# SER.net
KiCad netlist of a schematic drawn in Altium Designer
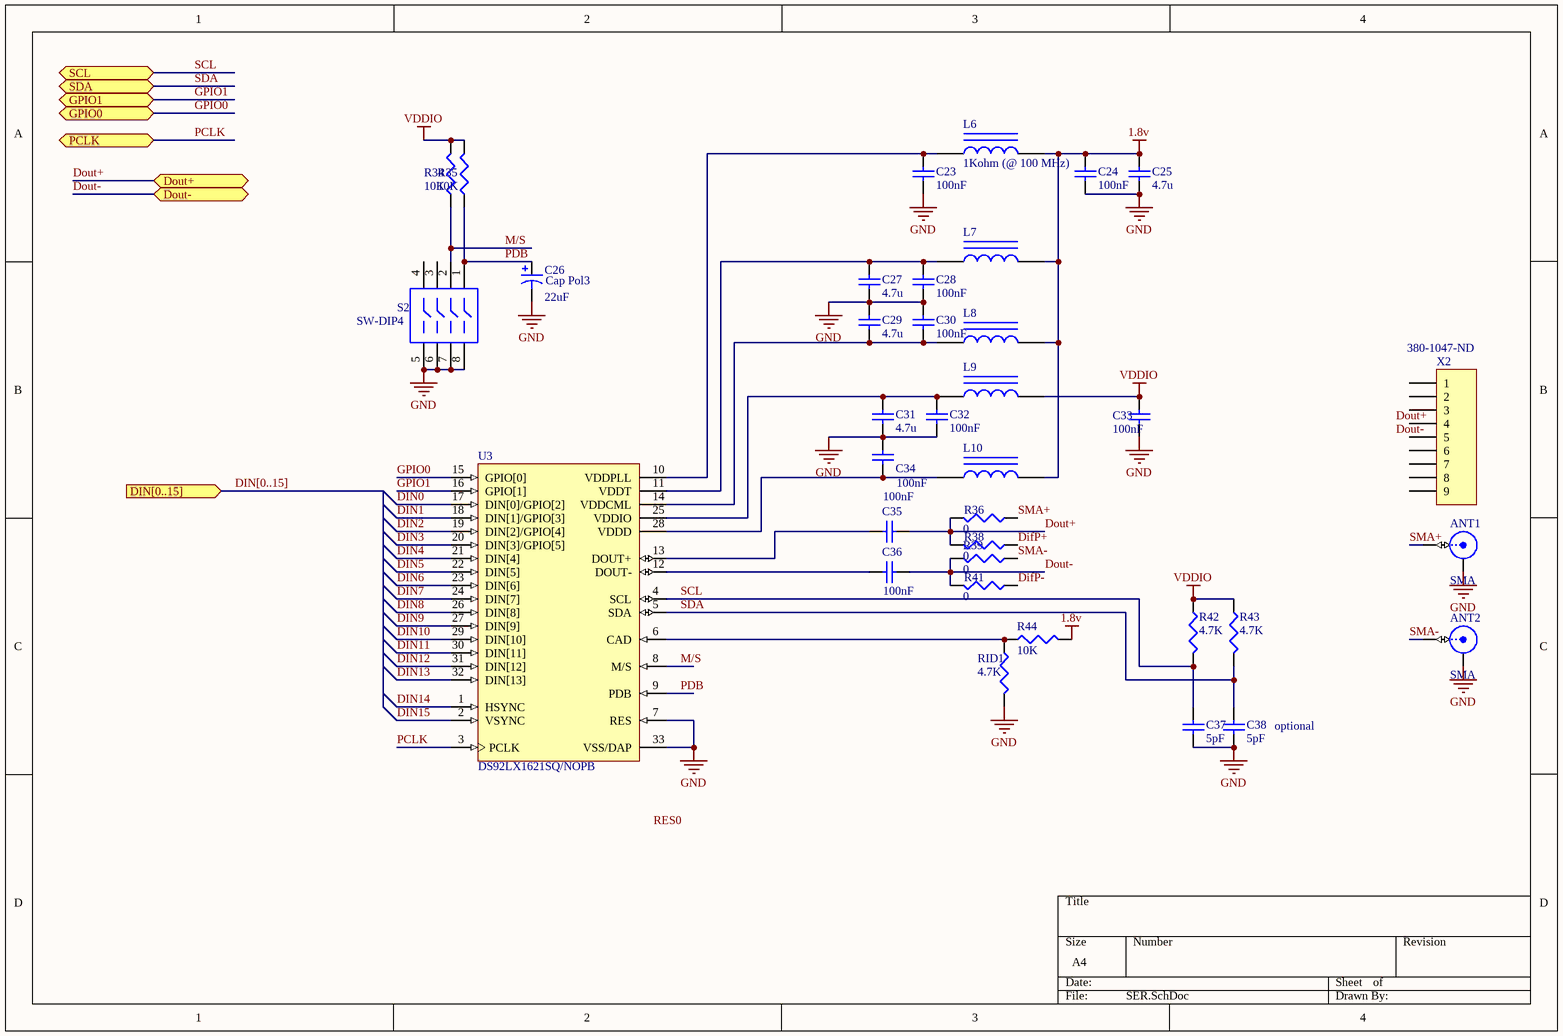
[diagram p0: SER.SchDoc]

(export (version "E")
  (design (tool "Eeschema 10.0.6"))
  (components
    (comp (ref "ANT1")
      (value "SMA")
      (footprint "SMB_V-RJ45")
      (description "SMA 50 Ohm Edge Mount")
      (libsource (lib "Connector_Div_egne") (part "SMA-J-P-H-ST-EM1"))
    )
    (comp (ref "ANT2")
      (value "SMA")
      (footprint "SMB_V-RJ45")
      (description "SMA 50 Ohm Edge Mount")
      (libsource (lib "Connector_Div_egne") (part "SMA-J-P-H-ST-EM1"))
    )
    (comp (ref "C23")
      (value "100nF")
      (footprint "1608[0603]")
      (description "Capacitor (Semiconductor SIM Model)")
      (fields (field (name "Comment") "Cap Semi") (field (name "PUBLISHER") "Altium Limited"))
      (libsource (lib "Miscellaneous Devices") (part "Cap Semi"))
    )
    (comp (ref "C24")
      (value "100nF")
      (footprint "1608[0603]")
      (description "Capacitor (Semiconductor SIM Model)")
      (fields (field (name "Comment") "Cap Semi") (field (name "PUBLISHER") "Altium Limited"))
      (libsource (lib "Miscellaneous Devices") (part "Cap Semi"))
    )
    (comp (ref "C25")
      (value "4.7u")
      (footprint "1608[0603]")
      (description "Capacitor (Semiconductor SIM Model)")
      (fields (field (name "Comment") "Cap Semi") (field (name "PUBLISHER") "Altium Limited"))
      (libsource (lib "Miscellaneous Devices") (part "Cap Semi"))
    )
    (comp (ref "C26")
      (value "Cap Pol3")
      (footprint "C0805")
      (description "Polarized Capacitor (Surface Mount)")
      (fields (field (name "ALTIUM_VALUE") "22uF") (field (name "PUBLISHER") "Altium Limited"))
      (libsource (lib "Miscellaneous Devices") (part "Cap Pol3"))
    )
    (comp (ref "C27")
      (value "4.7u")
      (footprint "1608[0603]")
      (description "Capacitor (Semiconductor SIM Model)")
      (fields (field (name "Comment") "Cap Semi") (field (name "PUBLISHER") "Altium Limited"))
      (libsource (lib "Miscellaneous Devices") (part "Cap Semi"))
    )
    (comp (ref "C28")
      (value "100nF")
      (footprint "1608[0603]")
      (description "Capacitor (Semiconductor SIM Model)")
      (fields (field (name "Comment") "Cap Semi") (field (name "PUBLISHER") "Altium Limited"))
      (libsource (lib "Miscellaneous Devices") (part "Cap Semi"))
    )
    (comp (ref "C29")
      (value "4.7u")
      (footprint "1608[0603]")
      (description "Capacitor (Semiconductor SIM Model)")
      (fields (field (name "Comment") "Cap Semi") (field (name "PUBLISHER") "Altium Limited"))
      (libsource (lib "Miscellaneous Devices") (part "Cap Semi"))
    )
    (comp (ref "C30")
      (value "100nF")
      (footprint "1608[0603]")
      (description "Capacitor (Semiconductor SIM Model)")
      (fields (field (name "Comment") "Cap Semi") (field (name "PUBLISHER") "Altium Limited"))
      (libsource (lib "Miscellaneous Devices") (part "Cap Semi"))
    )
    (comp (ref "C31")
      (value "4.7u")
      (footprint "1608[0603]")
      (description "Capacitor (Semiconductor SIM Model)")
      (fields (field (name "Comment") "Cap Semi") (field (name "PUBLISHER") "Altium Limited"))
      (libsource (lib "Miscellaneous Devices") (part "Cap Semi"))
    )
    (comp (ref "C32")
      (value "100nF")
      (footprint "1608[0603]")
      (description "Capacitor (Semiconductor SIM Model)")
      (fields (field (name "Comment") "Cap Semi") (field (name "PUBLISHER") "Altium Limited"))
      (libsource (lib "Miscellaneous Devices") (part "Cap Semi"))
    )
    (comp (ref "C33")
      (value "100nF")
      (footprint "1608[0603]")
      (description "Capacitor (Semiconductor SIM Model)")
      (fields (field (name "Comment") "Cap Semi") (field (name "PUBLISHER") "Altium Limited"))
      (libsource (lib "Miscellaneous Devices") (part "Cap Semi"))
    )
    (comp (ref "C34")
      (value "100nF")
      (footprint "1608[0603]")
      (description "Capacitor (Semiconductor SIM Model)")
      (fields (field (name "Comment") "Cap Semi") (field (name "PUBLISHER") "Altium Limited"))
      (libsource (lib "Miscellaneous Devices") (part "Cap Semi"))
    )
    (comp (ref "C35")
      (value "100nF")
      (footprint "1608[0603]")
      (description "CAP CER 0.1UF 50V X7R 0603")
      (fields (field (name "Comment") "Cap Semi") (field (name "PUBLISHER") "Altium Limited"))
      (libsource (lib "Miscellaneous Devices") (part "Cap Semi"))
    )
    (comp (ref "C36")
      (value "100nF")
      (footprint "1608[0603]")
      (description "CAP CER 0.1UF 50V X7R 0603")
      (fields (field (name "Comment") "Cap Semi") (field (name "PUBLISHER") "Altium Limited"))
      (libsource (lib "Miscellaneous Devices") (part "Cap Semi"))
    )
    (comp (ref "C37")
      (value "5pF")
      (footprint "1608[0603]")
      (description "Capacitor (Semiconductor SIM Model)")
      (fields (field (name "Comment") "Cap Semi") (field (name "PUBLISHER") "Altium Limited"))
      (libsource (lib "Miscellaneous Devices") (part "Cap Semi"))
    )
    (comp (ref "C38")
      (value "5pF")
      (footprint "1608[0603]")
      (description "Capacitor (Semiconductor SIM Model)")
      (fields (field (name "Comment") "Cap Semi") (field (name "PUBLISHER") "Altium Limited"))
      (libsource (lib "Miscellaneous Devices") (part "Cap Semi"))
    )
    (comp (ref "L6")
      (value "1Kohm (@ 100 MHz)")
      (footprint "0805")
      (description "Impedance = 1Kohm (@ 100 MHz)  low DC resistance (<1ohm)")
      (fields (field (name "PUBLISHER") "Altium Limited"))
      (libsource (lib "Miscellaneous Devices") (part "Inductor Iron"))
    )
    (comp (ref "L7")
      (value "~")
      (footprint "0805")
      (description "Impedance = 1 kohm (@ 100 MHz)  low DC resistance (<1ohm)")
      (fields (field (name "PUBLISHER") "Altium Limited"))
      (libsource (lib "Miscellaneous Devices") (part "Inductor Iron"))
    )
    (comp (ref "L8")
      (value "~")
      (footprint "0805")
      (description "Impedance = 1 kohm (@ 100 MHz)  low DC resistance (<1ohm)")
      (fields (field (name "PUBLISHER") "Altium Limited"))
      (libsource (lib "Miscellaneous Devices") (part "Inductor Iron"))
    )
    (comp (ref "L9")
      (value "~")
      (footprint "0805")
      (description "Impedance = 1 kohm (@ 100 MHz)  low DC resistance (<1ohm)")
      (fields (field (name "PUBLISHER") "Altium Limited"))
      (libsource (lib "Miscellaneous Devices") (part "Inductor Iron"))
    )
    (comp (ref "L10")
      (value "~")
      (footprint "0805")
      (description "Impedance = 1 kohm (@ 100 MHz)  low DC resistance (<1ohm)")
      (fields (field (name "PUBLISHER") "Altium Limited"))
      (libsource (lib "Miscellaneous Devices") (part "Inductor Iron"))
    )
    (comp (ref "R34")
      (value "10K")
      (footprint "12Z-2010")
      (description "Resistor")
      (fields (field (name "Comment") "Res3") (field (name "PUBLISHER") "Altium Limited"))
      (libsource (lib "Miscellaneous Devices") (part "Res3"))
    )
    (comp (ref "R35")
      (value "10K")
      (footprint "12Z-2010")
      (description "Resistor")
      (fields (field (name "Comment") "Res3") (field (name "PUBLISHER") "Altium Limited"))
      (libsource (lib "Miscellaneous Devices") (part "Res3"))
    )
    (comp (ref "R36")
      (value "0")
      (footprint "12Z-2010")
      (description "Resistor")
      (fields (field (name "Comment") "Res3") (field (name "PUBLISHER") "Altium Limited"))
      (libsource (lib "Miscellaneous Devices") (part "Res3"))
    )
    (comp (ref "R38")
      (value "0")
      (footprint "12Z-2010")
      (description "Resistor")
      (fields (field (name "Comment") "Res3") (field (name "PUBLISHER") "Altium Limited"))
      (libsource (lib "Miscellaneous Devices") (part "Res3"))
    )
    (comp (ref "R39")
      (value "0")
      (footprint "12Z-2010")
      (description "Resistor")
      (fields (field (name "Comment") "Res3") (field (name "PUBLISHER") "Altium Limited"))
      (libsource (lib "Miscellaneous Devices") (part "Res3"))
    )
    (comp (ref "R41")
      (value "0")
      (footprint "12Z-2010")
      (description "Resistor")
      (fields (field (name "Comment") "Res3") (field (name "PUBLISHER") "Altium Limited"))
      (libsource (lib "Miscellaneous Devices") (part "Res3"))
    )
    (comp (ref "R42")
      (value "4.7K")
      (footprint "12Z-2010")
      (description "Resistor")
      (fields (field (name "Comment") "Res3") (field (name "PUBLISHER") "Altium Limited"))
      (libsource (lib "Miscellaneous Devices") (part "Res3"))
    )
    (comp (ref "R43")
      (value "4.7K")
      (footprint "12Z-2010")
      (description "Resistor")
      (fields (field (name "Comment") "Res3") (field (name "PUBLISHER") "Altium Limited"))
      (libsource (lib "Miscellaneous Devices") (part "Res3"))
    )
    (comp (ref "R44")
      (value "10K")
      (footprint "12Z-2010")
      (description "Resistor")
      (fields (field (name "Comment") "Res3") (field (name "PUBLISHER") "Altium Limited"))
      (libsource (lib "Miscellaneous Devices") (part "Res3"))
    )
    (comp (ref "RID1")
      (value "4.7K")
      (footprint "12Z-2010")
      (description "Resistor")
      (fields (field (name "Comment") "Res3") (field (name "PUBLISHER") "Altium Limited"))
      (libsource (lib "Miscellaneous Devices") (part "Res3"))
    )
    (comp (ref "S2")
      (value "SW-DIP4")
      (footprint "DIP-8")
      (description "DIP Switch")
      (fields (field (name "PUBLISHER") "Altium Limited"))
      (libsource (lib "Miscellaneous Devices") (part "SW-DIP4"))
    )
    (comp (ref "U3")
      (value "DS92LX1621SQ/NOPB")
      (footprint "SQA32A")
      (description "10 - 50 MHz DC-Balanced Channel Link III Bi-Directional Control Serializer, 32 pin LLP")
      (fields
        (field (name "MANUFACTURER") "National Semiconductor")
        (field (name "PUBLISHER") "Altium Limited")
      )
      (libsource (lib "NSC Interface") (part "DS92LX1621SQ/NOPB"))
    )
    (comp (ref "X2")
      (value "SS-7188S-A-NF")
      (footprint "rj-45")
      (description "CONN MOD JACK 8P8C R/A SHIELDED")
      (fields
        (field (name "SUPPLIER PART NUMBER 1") "380-1047-ND")
        (field (name "MANUFACTURER") "Stewart Connector")
        (field (name "PUBLISHER") "Altium Limited")
      )
      (libsource (lib "Miscellaneous Connectors") (part "Header 9"))
    )
  )
  (nets
    (net (code "1") (name "/DIN0") (class "Default")
      (node (ref "U3") (pin "17") (pinfunction "DIN[0]/GPIO[2]_17") (pintype "input"))
    )
    (net (code "2") (name "/DIN1") (class "Default")
      (node (ref "U3") (pin "18") (pinfunction "DIN[1]/GPIO[3]_18") (pintype "input"))
    )
    (net (code "3") (name "/DIN2") (class "Default")
      (node (ref "U3") (pin "19") (pinfunction "DIN[2]/GPIO[4]_19") (pintype "input"))
    )
    (net (code "4") (name "/DIN3") (class "Default")
      (node (ref "U3") (pin "20") (pinfunction "DIN[3]/GPIO[5]_20") (pintype "input"))
    )
    (net (code "5") (name "/DIN4") (class "Default")
      (node (ref "U3") (pin "21") (pinfunction "DIN[4]_21") (pintype "input"))
    )
    (net (code "6") (name "/DIN5") (class "Default")
      (node (ref "U3") (pin "22") (pinfunction "DIN[5]_22") (pintype "input"))
    )
    (net (code "7") (name "/DIN6") (class "Default")
      (node (ref "U3") (pin "23") (pinfunction "DIN[6]_23") (pintype "input"))
    )
    (net (code "8") (name "/DIN7") (class "Default")
      (node (ref "U3") (pin "24") (pinfunction "DIN[7]_24") (pintype "input"))
    )
    (net (code "9") (name "/DIN8") (class "Default")
      (node (ref "U3") (pin "26") (pinfunction "DIN[8]_26") (pintype "input"))
    )
    (net (code "10") (name "/DIN9") (class "Default")
      (node (ref "U3") (pin "27") (pinfunction "DIN[9]_27") (pintype "input"))
    )
    (net (code "11") (name "/DIN10") (class "Default")
      (node (ref "U3") (pin "29") (pinfunction "DIN[10]_29") (pintype "input"))
    )
    (net (code "12") (name "/DIN11") (class "Default")
      (node (ref "U3") (pin "30") (pinfunction "DIN[11]_30") (pintype "input"))
    )
    (net (code "13") (name "/DIN12") (class "Default")
      (node (ref "U3") (pin "31") (pinfunction "DIN[12]_31") (pintype "input"))
    )
    (net (code "14") (name "/DIN13") (class "Default")
      (node (ref "U3") (pin "32") (pinfunction "DIN[13]_32") (pintype "input"))
    )
    (net (code "15") (name "/DIN14") (class "Default")
      (node (ref "U3") (pin "1") (pinfunction "HSYNC_1") (pintype "input"))
    )
    (net (code "16") (name "/DIN15") (class "Default")
      (node (ref "U3") (pin "2") (pinfunction "VSYNC_2") (pintype "input"))
    )
    (net (code "18") (name "/DifP+") (class "Default")
      (node (ref "R38") (pin "1") (pinfunction "1_1") (pintype "passive"))
    )
    (net (code "19") (name "/DifP-") (class "Default")
      (node (ref "R41") (pin "1") (pinfunction "1_1") (pintype "passive"))
    )
    (net (code "20") (name "/Dout+") (class "Default")
      (node (ref "C35") (pin "2") (pinfunction "2_2") (pintype "passive"))
      (node (ref "R36") (pin "2") (pinfunction "2_2") (pintype "passive"))
      (node (ref "R38") (pin "2") (pinfunction "2_2") (pintype "passive"))
    )
    (net (code "21") (name "/Dout-") (class "Default")
      (node (ref "C36") (pin "2") (pinfunction "2_2") (pintype "passive"))
      (node (ref "R39") (pin "2") (pinfunction "2_2") (pintype "passive"))
      (node (ref "R41") (pin "2") (pinfunction "2_2") (pintype "passive"))
    )
    (net (code "22") (name "/GPIO0") (class "Default")
      (node (ref "U3") (pin "15") (pinfunction "GPIO[0]_15") (pintype "input"))
    )
    (net (code "23") (name "/GPIO1") (class "Default")
      (node (ref "U3") (pin "16") (pinfunction "GPIO[1]_16") (pintype "input"))
    )
    (net (code "24") (name "/M{slash}S") (class "Default")
      (node (ref "R34") (pin "2") (pinfunction "2_2") (pintype "passive"))
      (node (ref "S2") (pin "2") (pinfunction "2_2") (pintype "passive"))
      (node (ref "U3") (pin "8") (pinfunction "M/S_8") (pintype "input"))
    )
    (net (code "25") (name "/PCLK") (class "Default")
      (node (ref "U3") (pin "3") (pinfunction "PCLK_3") (pintype "input"))
    )
    (net (code "26") (name "/PDB") (class "Default")
      (node (ref "C26") (pin "1") (pinfunction "1_1") (pintype "passive"))
      (node (ref "R35") (pin "2") (pinfunction "2_2") (pintype "passive"))
      (node (ref "S2") (pin "1") (pinfunction "1_1") (pintype "passive"))
      (node (ref "U3") (pin "9") (pinfunction "PDB_9") (pintype "input"))
    )
    (net (code "28") (name "/SCL") (class "Default")
      (node (ref "C37") (pin "2") (pinfunction "2_2") (pintype "passive"))
      (node (ref "R42") (pin "2") (pinfunction "2_2") (pintype "passive"))
      (node (ref "U3") (pin "4") (pinfunction "SCL_4") (pintype "bidirectional"))
    )
    (net (code "29") (name "/SDA") (class "Default")
      (node (ref "C38") (pin "2") (pinfunction "2_2") (pintype "passive"))
      (node (ref "R43") (pin "2") (pinfunction "2_2") (pintype "passive"))
      (node (ref "U3") (pin "5") (pinfunction "SDA_5") (pintype "bidirectional"))
    )
    (net (code "30") (name "/SMA+") (class "Default")
      (node (ref "ANT1") (pin "1") (pinfunction "IO_1") (pintype "bidirectional"))
      (node (ref "R36") (pin "1") (pinfunction "1_1") (pintype "passive"))
    )
    (net (code "31") (name "/SMA-") (class "Default")
      (node (ref "ANT2") (pin "1") (pinfunction "IO_1") (pintype "bidirectional"))
      (node (ref "R39") (pin "1") (pinfunction "1_1") (pintype "passive"))
    )
    (net (code "32") (name "1.8v") (class "Default")
      (node (ref "C24") (pin "2") (pinfunction "2_2") (pintype "passive"))
      (node (ref "C25") (pin "2") (pinfunction "2_2") (pintype "passive"))
      (node (ref "L10") (pin "2") (pinfunction "2_2") (pintype "passive"))
      (node (ref "L6") (pin "2") (pinfunction "2_2") (pintype "passive"))
      (node (ref "L7") (pin "2") (pinfunction "2_2") (pintype "passive"))
      (node (ref "L8") (pin "2") (pinfunction "2_2") (pintype "passive"))
      (node (ref "R44") (pin "2") (pinfunction "2_2") (pintype "passive"))
    )
    (net (code "33") (name "GND") (class "Default")
      (node (ref "ANT1") (pin "2") (pinfunction "Y_2") (pintype "power_in"))
      (node (ref "ANT2") (pin "2") (pinfunction "Y_2") (pintype "power_in"))
      (node (ref "C23") (pin "1") (pinfunction "1_1") (pintype "passive"))
      (node (ref "C24") (pin "1") (pinfunction "1_1") (pintype "passive"))
      (node (ref "C25") (pin "1") (pinfunction "1_1") (pintype "passive"))
      (node (ref "C26") (pin "2") (pinfunction "2_2") (pintype "passive"))
      (node (ref "C27") (pin "1") (pinfunction "1_1") (pintype "passive"))
      (node (ref "C28") (pin "1") (pinfunction "1_1") (pintype "passive"))
      (node (ref "C29") (pin "2") (pinfunction "2_2") (pintype "passive"))
      (node (ref "C30") (pin "2") (pinfunction "2_2") (pintype "passive"))
      (node (ref "C31") (pin "1") (pinfunction "1_1") (pintype "passive"))
      (node (ref "C32") (pin "1") (pinfunction "1_1") (pintype "passive"))
      (node (ref "C33") (pin "1") (pinfunction "1_1") (pintype "passive"))
      (node (ref "C34") (pin "2") (pinfunction "2_2") (pintype "passive"))
      (node (ref "C37") (pin "1") (pinfunction "1_1") (pintype "passive"))
      (node (ref "C38") (pin "1") (pinfunction "1_1") (pintype "passive"))
      (node (ref "RID1") (pin "2") (pinfunction "2_2") (pintype "passive"))
      (node (ref "S2") (pin "5") (pinfunction "5_5") (pintype "passive"))
      (node (ref "S2") (pin "6") (pinfunction "6_6") (pintype "passive"))
      (node (ref "S2") (pin "7") (pinfunction "7_7") (pintype "passive"))
      (node (ref "S2") (pin "8") (pinfunction "8_8") (pintype "passive"))
      (node (ref "U3") (pin "33") (pinfunction "VSS/DAP_33") (pintype "power_in"))
      (node (ref "U3") (pin "7") (pinfunction "RES_7") (pintype "input"))
    )
    (net (code "34") (name "Net-(U3-CAD)") (class "Default")
      (node (ref "R44") (pin "1") (pinfunction "1_1") (pintype "passive"))
      (node (ref "RID1") (pin "1") (pinfunction "1_1") (pintype "passive"))
      (node (ref "U3") (pin "6") (pinfunction "CAD_6") (pintype "input"))
    )
    (net (code "35") (name "Net-(U3-DOUT+)") (class "Default")
      (node (ref "C35") (pin "1") (pinfunction "1_1") (pintype "passive"))
      (node (ref "U3") (pin "13") (pinfunction "DOUT+_13") (pintype "bidirectional"))
    )
    (net (code "36") (name "Net-(U3-DOUT-)") (class "Default")
      (node (ref "C36") (pin "1") (pinfunction "1_1") (pintype "passive"))
      (node (ref "U3") (pin "12") (pinfunction "DOUT-_12") (pintype "bidirectional"))
    )
    (net (code "37") (name "Net-(U3-VDDCML)") (class "Default")
      (node (ref "C29") (pin "1") (pinfunction "1_1") (pintype "passive"))
      (node (ref "C30") (pin "1") (pinfunction "1_1") (pintype "passive"))
      (node (ref "L8") (pin "1") (pinfunction "1_1") (pintype "passive"))
      (node (ref "U3") (pin "14") (pinfunction "VDDCML_14") (pintype "power_in"))
    )
    (net (code "38") (name "Net-(U3-VDDD)") (class "Default")
      (node (ref "C34") (pin "1") (pinfunction "1_1") (pintype "passive"))
      (node (ref "L10") (pin "1") (pinfunction "1_1") (pintype "passive"))
      (node (ref "U3") (pin "28") (pinfunction "VDDD_28") (pintype "power_in"))
    )
    (net (code "39") (name "Net-(U3-VDDIO)") (class "Default")
      (node (ref "C31") (pin "2") (pinfunction "2_2") (pintype "passive"))
      (node (ref "C32") (pin "2") (pinfunction "2_2") (pintype "passive"))
      (node (ref "L9") (pin "1") (pinfunction "1_1") (pintype "passive"))
      (node (ref "U3") (pin "25") (pinfunction "VDDIO_25") (pintype "power_in"))
    )
    (net (code "40") (name "Net-(U3-VDDPLL)") (class "Default")
      (node (ref "C23") (pin "2") (pinfunction "2_2") (pintype "passive"))
      (node (ref "L6") (pin "1") (pinfunction "1_1") (pintype "passive"))
      (node (ref "U3") (pin "10") (pinfunction "VDDPLL_10") (pintype "power_in"))
    )
    (net (code "41") (name "Net-(U3-VDDT)") (class "Default")
      (node (ref "C27") (pin "2") (pinfunction "2_2") (pintype "passive"))
      (node (ref "C28") (pin "2") (pinfunction "2_2") (pintype "passive"))
      (node (ref "L7") (pin "1") (pinfunction "1_1") (pintype "passive"))
      (node (ref "U3") (pin "11") (pinfunction "VDDT_11") (pintype "power_in"))
    )
    (net (code "42") (name "VDDIO") (class "Default")
      (node (ref "C33") (pin "2") (pinfunction "2_2") (pintype "passive"))
      (node (ref "L9") (pin "2") (pinfunction "2_2") (pintype "passive"))
      (node (ref "R34") (pin "1") (pinfunction "1_1") (pintype "passive"))
      (node (ref "R35") (pin "1") (pinfunction "1_1") (pintype "passive"))
      (node (ref "R42") (pin "1") (pinfunction "1_1") (pintype "passive"))
      (node (ref "R43") (pin "1") (pinfunction "1_1") (pintype "passive"))
    )
    (net (code "43") (name "unconnected-(S2-Pad3)") (class "Default")
      (node (ref "S2") (pin "3") (pinfunction "3_3") (pintype "passive"))
    )
    (net (code "44") (name "unconnected-(S2-Pad4)") (class "Default")
      (node (ref "S2") (pin "4") (pinfunction "4_4") (pintype "passive"))
    )
    (net (code "45") (name "unconnected-(X2-Pad1)") (class "Default")
      (node (ref "X2") (pin "1") (pinfunction "1_1") (pintype "passive"))
    )
    (net (code "46") (name "unconnected-(X2-Pad2)") (class "Default")
      (node (ref "X2") (pin "2") (pinfunction "2_2") (pintype "passive"))
    )
    (net (code "47") (name "unconnected-(X2-Pad3)") (class "Default")
      (node (ref "X2") (pin "3") (pinfunction "3_3") (pintype "passive"))
    )
    (net (code "48") (name "unconnected-(X2-Pad4)") (class "Default")
      (node (ref "X2") (pin "4") (pinfunction "4_4") (pintype "passive"))
    )
    (net (code "49") (name "unconnected-(X2-Pad5)") (class "Default")
      (node (ref "X2") (pin "5") (pinfunction "5_5") (pintype "passive"))
    )
    (net (code "50") (name "unconnected-(X2-Pad6)") (class "Default")
      (node (ref "X2") (pin "6") (pinfunction "6_6") (pintype "passive"))
    )
    (net (code "51") (name "unconnected-(X2-Pad7)") (class "Default")
      (node (ref "X2") (pin "7") (pinfunction "7_7") (pintype "passive"))
    )
    (net (code "52") (name "unconnected-(X2-Pad8)") (class "Default")
      (node (ref "X2") (pin "8") (pinfunction "8_8") (pintype "passive"))
    )
    (net (code "53") (name "unconnected-(X2-Pad9)") (class "Default")
      (node (ref "X2") (pin "9") (pinfunction "9_9") (pintype "passive"))
    )
  )
)
